# Cassette_Port.net
KiCad netlist of a schematic drawn in EAGLE
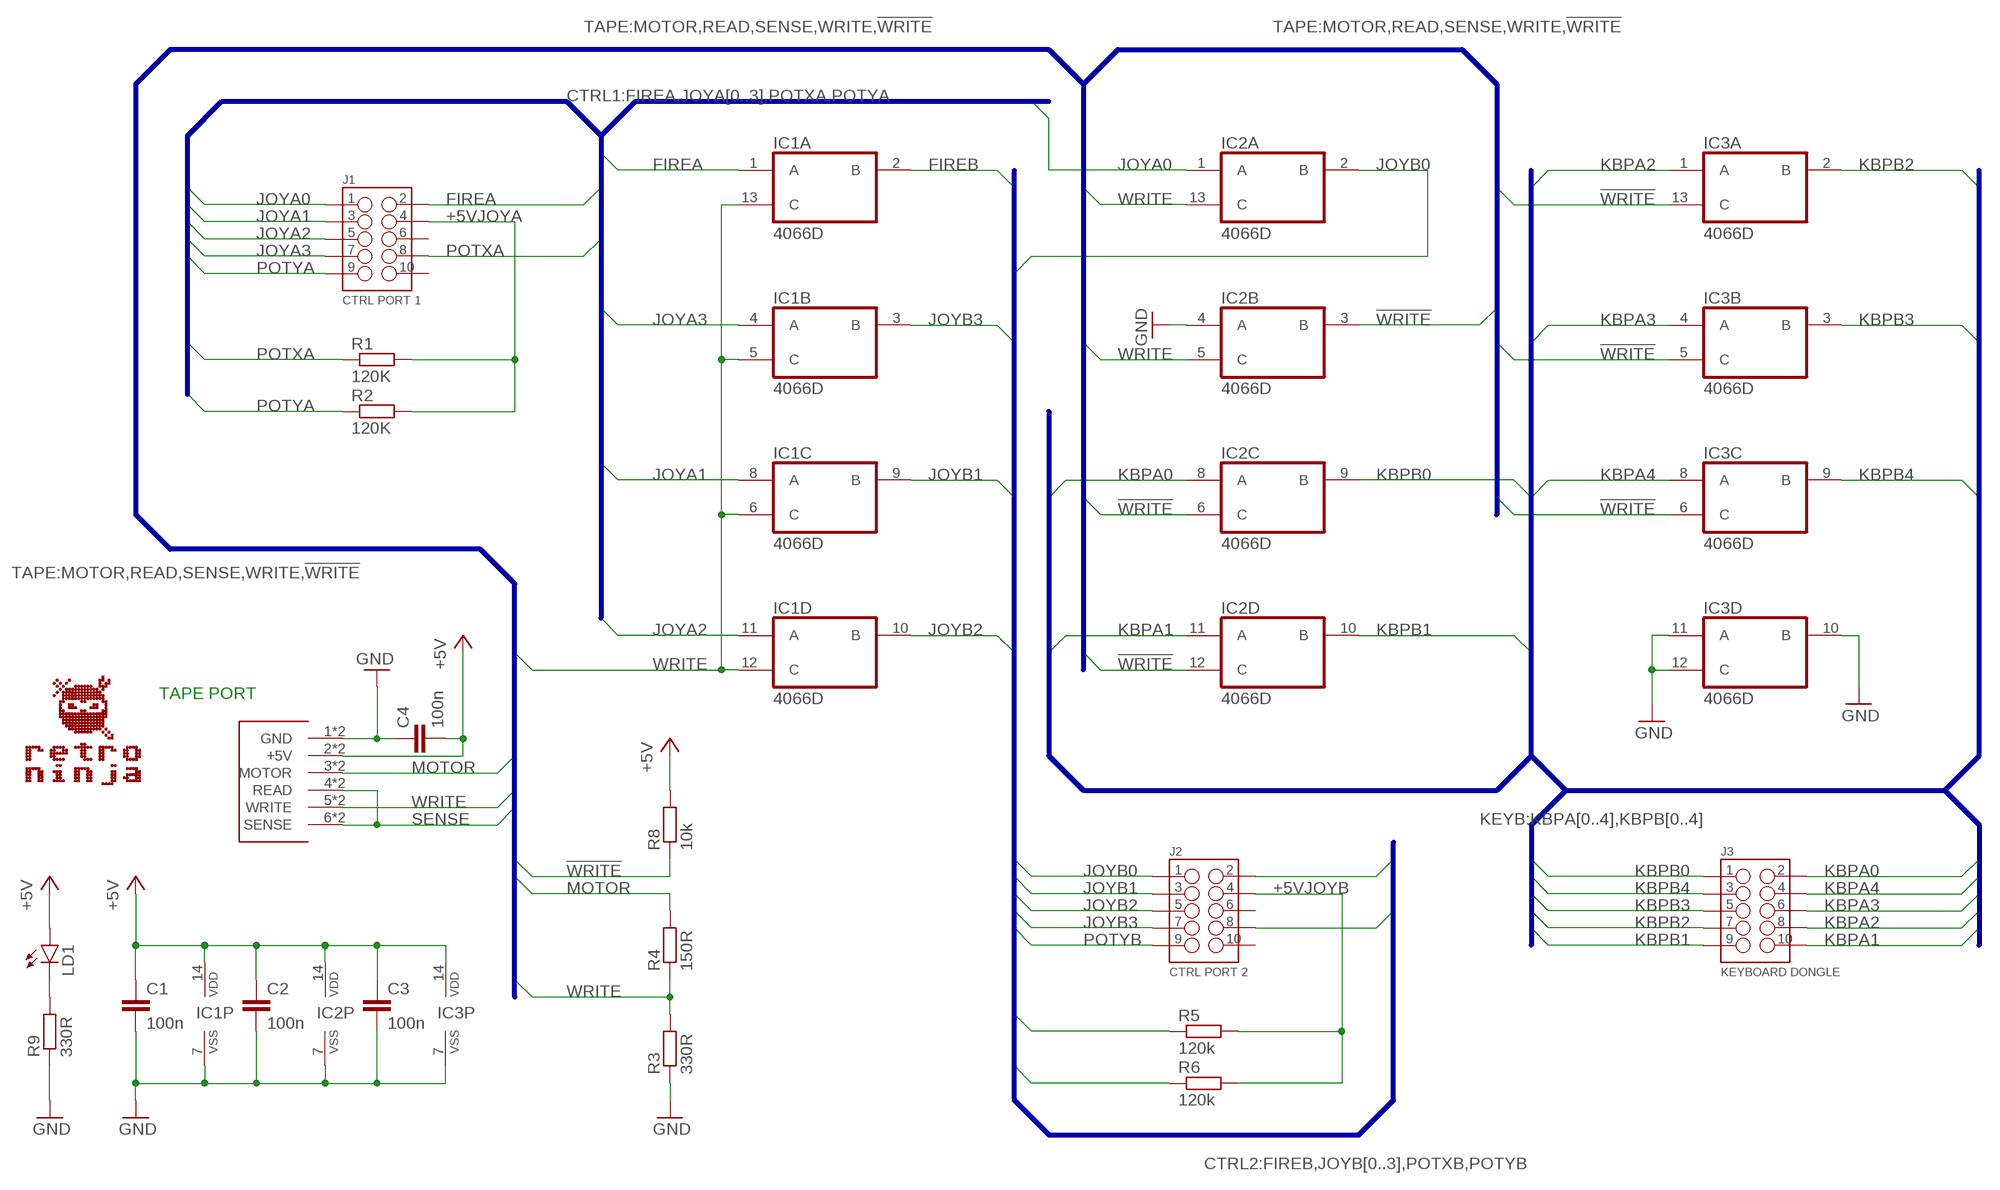
[diagram p0: schematic, sheet 1]

(export (version "E")
  (design (tool "Eeschema 10.0.6"))
  (components
    (comp (ref "C1")
      (value "100n")
      (footprint "eagle-import:C0805")
      (libsource (lib "eagle-import") (part "C-EUC0805"))
    )
    (comp (ref "C2")
      (value "100n")
      (footprint "eagle-import:C0805")
      (libsource (lib "eagle-import") (part "C-EUC0805"))
    )
    (comp (ref "C3")
      (value "100n")
      (footprint "eagle-import:C0805")
      (libsource (lib "eagle-import") (part "C-EUC0805"))
    )
    (comp (ref "C4")
      (value "100n")
      (footprint "eagle-import:C0805")
      (libsource (lib "eagle-import") (part "C-EUC0805"))
    )
    (comp (ref "CN1")
      (value "C64_CASSETTE_PORT_CONNECTOR_SIDE")
      (footprint "eagle-import:C64_CASSETTE_CONNECTOR")
      (libsource (lib "eagle-import") (part "C64_CASSETTE_PORT_CONNECTOR_SIDE"))
    )
    (comp (ref "IC1")
      (value "4066D")
      (footprint "eagle-import:SO14")
      (libsource (lib "eagle-import") (part "4066D"))
    )
    (comp (ref "IC2")
      (value "4066D")
      (footprint "eagle-import:SO14")
      (libsource (lib "eagle-import") (part "4066D"))
    )
    (comp (ref "IC3")
      (value "4066D")
      (footprint "eagle-import:SO14")
      (libsource (lib "eagle-import") (part "4066D"))
    )
    (comp (ref "J1")
      (value "CTRL PORT 1")
      (footprint "eagle-import:2X5_HEADER_WALLED")
      (libsource (lib "eagle-import") (part "HEADER_2X5-WALLED"))
    )
    (comp (ref "J2")
      (value "CTRL PORT 2")
      (footprint "eagle-import:2X5_HEADER_WALLED")
      (libsource (lib "eagle-import") (part "HEADER_2X5-WALLED"))
    )
    (comp (ref "J3")
      (value "KEYBOARD DONGLE")
      (footprint "eagle-import:2X5_HEADER_WALLED")
      (libsource (lib "eagle-import") (part "HEADER_2X5-WALLED"))
    )
    (comp (ref "LD1")
      (value "LED3MM")
      (footprint "eagle-import:LED3MM")
      (libsource (lib "eagle-import") (part "LED3MM"))
    )
    (comp (ref "R1")
      (value "120K")
      (footprint "eagle-import:R0805")
      (libsource (lib "eagle-import") (part "R-EU_R0805"))
    )
    (comp (ref "R2")
      (value "120K")
      (footprint "eagle-import:R0805")
      (libsource (lib "eagle-import") (part "R-EU_R0805"))
    )
    (comp (ref "R3")
      (value "330R")
      (footprint "eagle-import:R0805")
      (libsource (lib "eagle-import") (part "R-EU_R0805"))
    )
    (comp (ref "R4")
      (value "150R")
      (footprint "eagle-import:R0805")
      (libsource (lib "eagle-import") (part "R-EU_R0805"))
    )
    (comp (ref "R5")
      (value "120k")
      (footprint "eagle-import:R0805")
      (libsource (lib "eagle-import") (part "R-EU_R0805"))
    )
    (comp (ref "R6")
      (value "120k")
      (footprint "eagle-import:R0805")
      (libsource (lib "eagle-import") (part "R-EU_R0805"))
    )
    (comp (ref "R8")
      (value "10k")
      (footprint "eagle-import:R0805")
      (libsource (lib "eagle-import") (part "R-EU_R0805"))
    )
    (comp (ref "R9")
      (value "330R")
      (footprint "eagle-import:R0805")
      (libsource (lib "eagle-import") (part "R-EU_R0805"))
    )
    (comp (ref "U$1")
      (value "RETRONINJA_TEXT")
      (footprint "eagle-import:RETRONINJA_TEXT_17MM")
      (libsource (lib "eagle-import") (part "RETRONINJA_TEXT"))
    )
  )
  (nets
    (net (code "5") (name "+5V") (class "Default")
      (node (ref "C1") (pin "1") (pinfunction "1_1") (pintype "passive"))
      (node (ref "C2") (pin "1") (pinfunction "1_1") (pintype "passive"))
      (node (ref "C3") (pin "1") (pinfunction "1_1") (pintype "passive"))
      (node (ref "C4") (pin "2") (pinfunction "2_2") (pintype "passive"))
      (node (ref "CN1") (pin "2") (pinfunction "+5V_2") (pintype "power_in"))
      (node (ref "CN1") (pin "B") (pinfunction "+5V_B") (pintype "power_in"))
      (node (ref "IC1") (pin "14") (pinfunction "VDD_14") (pintype "power_in"))
      (node (ref "IC2") (pin "14") (pinfunction "VDD_14") (pintype "power_in"))
      (node (ref "IC3") (pin "14") (pinfunction "VDD_14") (pintype "power_in"))
      (node (ref "LD1") (pin "A") (pinfunction "A_A") (pintype "passive"))
      (node (ref "R8") (pin "2") (pinfunction "2_2") (pintype "passive"))
    )
    (net (code "6") (name "/+5VJOYA") (class "Default")
      (node (ref "J1") (pin "4") (pinfunction "4_4") (pintype "bidirectional"))
      (node (ref "R1") (pin "2") (pinfunction "2_2") (pintype "passive"))
      (node (ref "R2") (pin "2") (pinfunction "2_2") (pintype "passive"))
    )
    (net (code "7") (name "/+5VJOYB") (class "Default")
      (node (ref "J2") (pin "4") (pinfunction "4_4") (pintype "bidirectional"))
      (node (ref "R5") (pin "2") (pinfunction "2_2") (pintype "passive"))
      (node (ref "R6") (pin "2") (pinfunction "2_2") (pintype "passive"))
    )
    (net (code "8") (name "/FIREA") (class "Default")
      (node (ref "IC1") (pin "1") (pinfunction "A_1") (pintype "tri_state"))
      (node (ref "J1") (pin "2") (pinfunction "2_2") (pintype "bidirectional"))
    )
    (net (code "9") (name "/FIREB") (class "Default")
      (node (ref "IC1") (pin "2") (pinfunction "B_2") (pintype "tri_state"))
      (node (ref "J2") (pin "2") (pinfunction "2_2") (pintype "bidirectional"))
    )
    (net (code "10") (name "/JOYA0") (class "Default")
      (node (ref "IC2") (pin "1") (pinfunction "A_1") (pintype "tri_state"))
      (node (ref "J1") (pin "1") (pinfunction "1_1") (pintype "bidirectional"))
    )
    (net (code "11") (name "/JOYA1") (class "Default")
      (node (ref "IC1") (pin "8") (pinfunction "A_8") (pintype "tri_state"))
      (node (ref "J1") (pin "3") (pinfunction "3_3") (pintype "bidirectional"))
    )
    (net (code "12") (name "/JOYA2") (class "Default")
      (node (ref "IC1") (pin "11") (pinfunction "A_11") (pintype "tri_state"))
      (node (ref "J1") (pin "5") (pinfunction "5_5") (pintype "bidirectional"))
    )
    (net (code "13") (name "/JOYA3") (class "Default")
      (node (ref "IC1") (pin "4") (pinfunction "A_4") (pintype "tri_state"))
      (node (ref "J1") (pin "7") (pinfunction "7_7") (pintype "bidirectional"))
    )
    (net (code "14") (name "/JOYB0") (class "Default")
      (node (ref "IC2") (pin "2") (pinfunction "B_2") (pintype "tri_state"))
      (node (ref "J2") (pin "1") (pinfunction "1_1") (pintype "bidirectional"))
    )
    (net (code "15") (name "/JOYB1") (class "Default")
      (node (ref "IC1") (pin "9") (pinfunction "B_9") (pintype "tri_state"))
      (node (ref "J2") (pin "3") (pinfunction "3_3") (pintype "bidirectional"))
    )
    (net (code "16") (name "/JOYB2") (class "Default")
      (node (ref "IC1") (pin "10") (pinfunction "B_10") (pintype "tri_state"))
      (node (ref "J2") (pin "5") (pinfunction "5_5") (pintype "bidirectional"))
    )
    (net (code "17") (name "/JOYB3") (class "Default")
      (node (ref "IC1") (pin "3") (pinfunction "B_3") (pintype "tri_state"))
      (node (ref "J2") (pin "7") (pinfunction "7_7") (pintype "bidirectional"))
    )
    (net (code "18") (name "/KBPA0") (class "Default")
      (node (ref "IC2") (pin "8") (pinfunction "A_8") (pintype "tri_state"))
      (node (ref "J3") (pin "2") (pinfunction "2_2") (pintype "bidirectional"))
    )
    (net (code "19") (name "/KBPA1") (class "Default")
      (node (ref "IC2") (pin "11") (pinfunction "A_11") (pintype "tri_state"))
      (node (ref "J3") (pin "10") (pinfunction "10_10") (pintype "bidirectional"))
    )
    (net (code "20") (name "/KBPA2") (class "Default")
      (node (ref "IC3") (pin "1") (pinfunction "A_1") (pintype "tri_state"))
      (node (ref "J3") (pin "8") (pinfunction "8_8") (pintype "bidirectional"))
    )
    (net (code "21") (name "/KBPA3") (class "Default")
      (node (ref "IC3") (pin "4") (pinfunction "A_4") (pintype "tri_state"))
      (node (ref "J3") (pin "6") (pinfunction "6_6") (pintype "bidirectional"))
    )
    (net (code "22") (name "/KBPA4") (class "Default")
      (node (ref "IC3") (pin "8") (pinfunction "A_8") (pintype "tri_state"))
      (node (ref "J3") (pin "4") (pinfunction "4_4") (pintype "bidirectional"))
    )
    (net (code "23") (name "/KBPB0") (class "Default")
      (node (ref "IC2") (pin "9") (pinfunction "B_9") (pintype "tri_state"))
      (node (ref "J3") (pin "1") (pinfunction "1_1") (pintype "bidirectional"))
    )
    (net (code "24") (name "/KBPB1") (class "Default")
      (node (ref "IC2") (pin "10") (pinfunction "B_10") (pintype "tri_state"))
      (node (ref "J3") (pin "9") (pinfunction "9_9") (pintype "bidirectional"))
    )
    (net (code "25") (name "/KBPB2") (class "Default")
      (node (ref "IC3") (pin "2") (pinfunction "B_2") (pintype "tri_state"))
      (node (ref "J3") (pin "7") (pinfunction "7_7") (pintype "bidirectional"))
    )
    (net (code "26") (name "/KBPB3") (class "Default")
      (node (ref "IC3") (pin "3") (pinfunction "B_3") (pintype "tri_state"))
      (node (ref "J3") (pin "5") (pinfunction "5_5") (pintype "bidirectional"))
    )
    (net (code "27") (name "/KBPB4") (class "Default")
      (node (ref "IC3") (pin "9") (pinfunction "B_9") (pintype "tri_state"))
      (node (ref "J3") (pin "3") (pinfunction "3_3") (pintype "bidirectional"))
    )
    (net (code "28") (name "/MOTOR") (class "Default")
      (node (ref "CN1") (pin "3") (pinfunction "MOTOR_3") (pintype "bidirectional"))
      (node (ref "CN1") (pin "C") (pinfunction "MOTOR_C") (pintype "bidirectional"))
      (node (ref "R4") (pin "2") (pinfunction "2_2") (pintype "passive"))
    )
    (net (code "29") (name "/POTXA") (class "Default")
      (node (ref "J1") (pin "8") (pinfunction "8_8") (pintype "bidirectional"))
      (node (ref "R1") (pin "1") (pinfunction "1_1") (pintype "passive"))
    )
    (net (code "30") (name "/POTXB") (class "Default")
      (node (ref "J2") (pin "8") (pinfunction "8_8") (pintype "bidirectional"))
      (node (ref "R5") (pin "1") (pinfunction "1_1") (pintype "passive"))
    )
    (net (code "31") (name "/POTYA") (class "Default")
      (node (ref "J1") (pin "9") (pinfunction "9_9") (pintype "bidirectional"))
      (node (ref "R2") (pin "1") (pinfunction "1_1") (pintype "passive"))
    )
    (net (code "32") (name "/POTYB") (class "Default")
      (node (ref "J2") (pin "9") (pinfunction "9_9") (pintype "bidirectional"))
      (node (ref "R6") (pin "1") (pinfunction "1_1") (pintype "passive"))
    )
    (net (code "33") (name "/SENSE") (class "Default")
      (node (ref "CN1") (pin "4") (pinfunction "READ_4") (pintype "bidirectional"))
      (node (ref "CN1") (pin "6") (pinfunction "SENSE_6") (pintype "bidirectional"))
      (node (ref "CN1") (pin "D") (pinfunction "READ_D") (pintype "bidirectional"))
      (node (ref "CN1") (pin "F") (pinfunction "SENSE_F") (pintype "bidirectional"))
    )
    (net (code "34") (name "/WRITE") (class "Default")
      (node (ref "CN1") (pin "5") (pinfunction "WRITE_5") (pintype "bidirectional"))
      (node (ref "CN1") (pin "E") (pinfunction "WRITE_E") (pintype "bidirectional"))
      (node (ref "IC1") (pin "12") (pinfunction "C_12") (pintype "input"))
      (node (ref "IC1") (pin "13") (pinfunction "C_13") (pintype "input"))
      (node (ref "IC1") (pin "5") (pinfunction "C_5") (pintype "input"))
      (node (ref "IC1") (pin "6") (pinfunction "C_6") (pintype "input"))
      (node (ref "IC2") (pin "13") (pinfunction "C_13") (pintype "input"))
      (node (ref "IC2") (pin "5") (pinfunction "C_5") (pintype "input"))
      (node (ref "R3") (pin "2") (pinfunction "2_2") (pintype "passive"))
      (node (ref "R4") (pin "1") (pinfunction "1_1") (pintype "passive"))
    )
    (net (code "39") (name "/~{WRITE}") (class "Default")
      (node (ref "IC2") (pin "12") (pinfunction "C_12") (pintype "input"))
      (node (ref "IC2") (pin "3") (pinfunction "B_3") (pintype "tri_state"))
      (node (ref "IC2") (pin "6") (pinfunction "C_6") (pintype "input"))
      (node (ref "IC3") (pin "13") (pinfunction "C_13") (pintype "input"))
      (node (ref "IC3") (pin "5") (pinfunction "C_5") (pintype "input"))
      (node (ref "IC3") (pin "6") (pinfunction "C_6") (pintype "input"))
      (node (ref "R8") (pin "1") (pinfunction "1_1") (pintype "passive"))
    )
    (net (code "40") (name "GND") (class "Default")
      (node (ref "C1") (pin "2") (pinfunction "2_2") (pintype "passive"))
      (node (ref "C2") (pin "2") (pinfunction "2_2") (pintype "passive"))
      (node (ref "C3") (pin "2") (pinfunction "2_2") (pintype "passive"))
      (node (ref "C4") (pin "1") (pinfunction "1_1") (pintype "passive"))
      (node (ref "CN1") (pin "1") (pinfunction "GND_1") (pintype "power_in"))
      (node (ref "CN1") (pin "A") (pinfunction "GND_A") (pintype "power_in"))
      (node (ref "IC1") (pin "7") (pinfunction "VSS_7") (pintype "power_in"))
      (node (ref "IC2") (pin "4") (pinfunction "A_4") (pintype "tri_state"))
      (node (ref "IC2") (pin "7") (pinfunction "VSS_7") (pintype "power_in"))
      (node (ref "IC3") (pin "10") (pinfunction "B_10") (pintype "tri_state"))
      (node (ref "IC3") (pin "11") (pinfunction "A_11") (pintype "tri_state"))
      (node (ref "IC3") (pin "12") (pinfunction "C_12") (pintype "input"))
      (node (ref "IC3") (pin "7") (pinfunction "VSS_7") (pintype "power_in"))
      (node (ref "R3") (pin "1") (pinfunction "1_1") (pintype "passive"))
      (node (ref "R9") (pin "1") (pinfunction "1_1") (pintype "passive"))
    )
    (net (code "41") (name "Net-(LD1-C)") (class "Default")
      (node (ref "LD1") (pin "K") (pinfunction "C_K") (pintype "passive"))
      (node (ref "R9") (pin "2") (pinfunction "2_2") (pintype "passive"))
    )
    (net (code "42") (name "unconnected-(J1-Pad6)") (class "Default")
      (node (ref "J1") (pin "6") (pinfunction "6_6") (pintype "bidirectional"))
    )
    (net (code "43") (name "unconnected-(J1-Pad10)") (class "Default")
      (node (ref "J1") (pin "10") (pinfunction "10_10") (pintype "bidirectional"))
    )
    (net (code "44") (name "unconnected-(J2-Pad6)") (class "Default")
      (node (ref "J2") (pin "6") (pinfunction "6_6") (pintype "bidirectional"))
    )
    (net (code "45") (name "unconnected-(J2-Pad10)") (class "Default")
      (node (ref "J2") (pin "10") (pinfunction "10_10") (pintype "bidirectional"))
    )
  )
)
